# DVI.net
KiCad netlist of a schematic drawn in Altium Designer
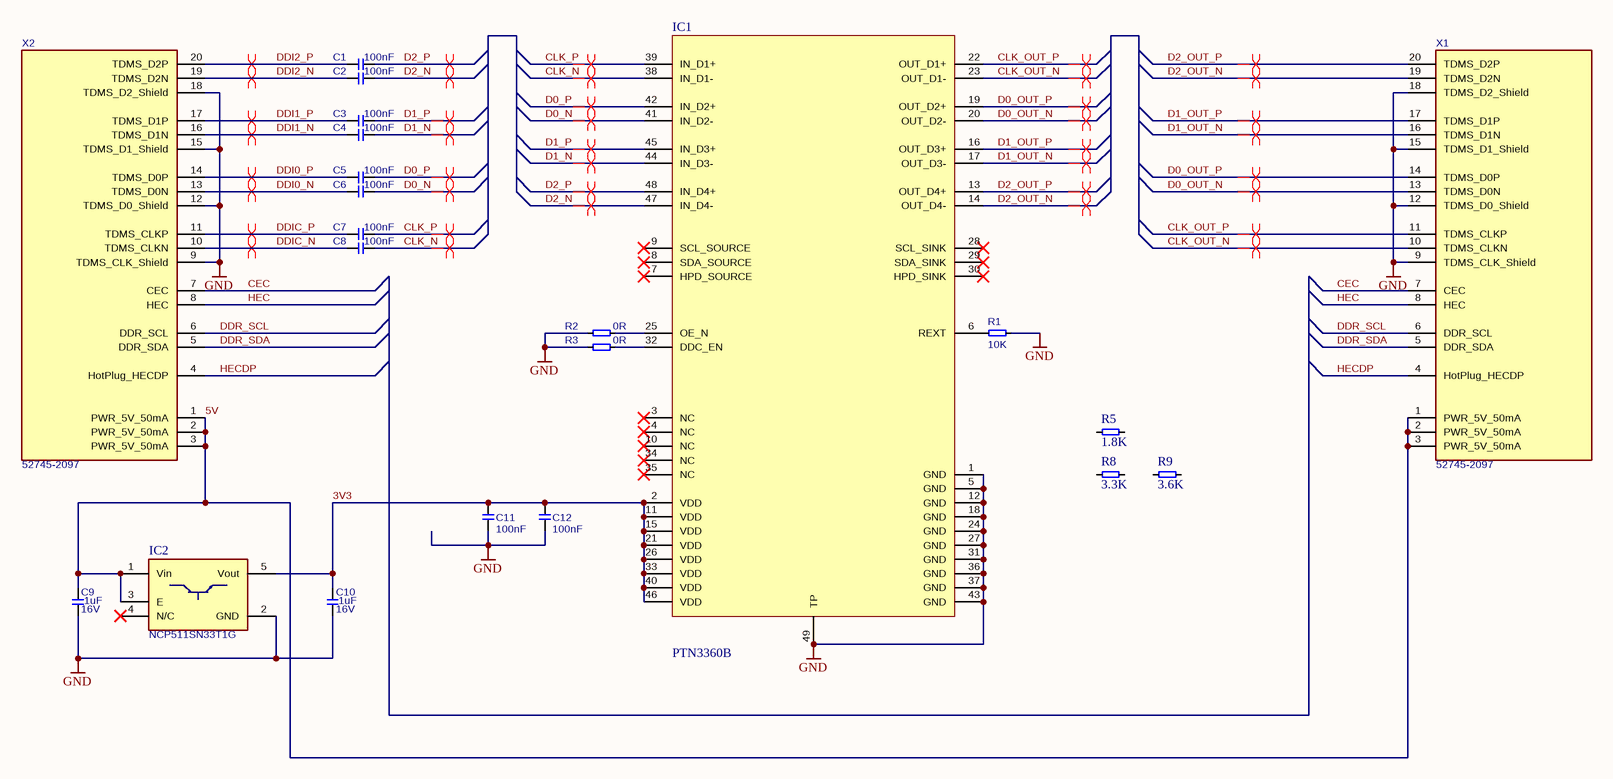
[diagram p0: DVI.SchDoc]

(export (version "E")
  (design (tool "Eeschema 10.0.6"))
  (components
    (comp (ref "C1")
      (value "100nF")
      (footprint "T_CAPC0603X33N")
      (description "Capacitor Ceramic X7R 100nF 16V 10% 0402")
      (fields (field (name "TOLERANCE") "10%"))
      (libsource (lib "Apalis Evaluation Board") (part "C-X7R-100nF-16V-10%-0402"))
    )
    (comp (ref "C2")
      (value "100nF")
      (footprint "T_CAPC0603X33N")
      (description "Capacitor Ceramic X7R 100nF 16V 10% 0402")
      (fields (field (name "TOLERANCE") "10%"))
      (libsource (lib "Apalis Evaluation Board") (part "C-X7R-100nF-16V-10%-0402"))
    )
    (comp (ref "C3")
      (value "100nF")
      (footprint "T_CAPC0603X33N")
      (description "Capacitor Ceramic X7R 100nF 16V 10% 0402")
      (fields (field (name "TOLERANCE") "10%"))
      (libsource (lib "Apalis Evaluation Board") (part "C-X7R-100nF-16V-10%-0402"))
    )
    (comp (ref "C4")
      (value "100nF")
      (footprint "T_CAPC0603X33N")
      (description "Capacitor Ceramic X7R 100nF 16V 10% 0402")
      (fields (field (name "TOLERANCE") "10%"))
      (libsource (lib "Apalis Evaluation Board") (part "C-X7R-100nF-16V-10%-0402"))
    )
    (comp (ref "C5")
      (value "100nF")
      (footprint "T_CAPC0603X33N")
      (description "Capacitor Ceramic X7R 100nF 16V 10% 0402")
      (fields (field (name "TOLERANCE") "10%"))
      (libsource (lib "Apalis Evaluation Board") (part "C-X7R-100nF-16V-10%-0402"))
    )
    (comp (ref "C6")
      (value "100nF")
      (footprint "T_CAPC0603X33N")
      (description "Capacitor Ceramic X7R 100nF 16V 10% 0402")
      (fields (field (name "TOLERANCE") "10%"))
      (libsource (lib "Apalis Evaluation Board") (part "C-X7R-100nF-16V-10%-0402"))
    )
    (comp (ref "C7")
      (value "100nF")
      (footprint "T_CAPC0603X33N")
      (description "Capacitor Ceramic X7R 100nF 16V 10% 0402")
      (fields (field (name "TOLERANCE") "10%"))
      (libsource (lib "Apalis Evaluation Board") (part "C-X7R-100nF-16V-10%-0402"))
    )
    (comp (ref "C8")
      (value "100nF")
      (footprint "T_CAPC0603X33N")
      (description "Capacitor Ceramic X7R 100nF 16V 10% 0402")
      (fields (field (name "TOLERANCE") "10%"))
      (libsource (lib "Apalis Evaluation Board") (part "C-X7R-100nF-16V-10%-0402"))
    )
    (comp (ref "C9")
      (value "1uF")
      (footprint "T_CAPC0603X33N")
      (description "Capacitor Ceramic X5R 1uF 16V 20% 0603")
      (fields (field (name "TOLERANCE") "20%") (field (name "RATING") "16V"))
      (libsource (lib "Apalis Evaluation Board") (part "C-X5R-1uF-16V-20%-0603"))
    )
    (comp (ref "C10")
      (value "1uF")
      (footprint "T_CAPC0603X33N")
      (description "Capacitor Ceramic X5R 1uF 16V 20% 0603")
      (fields (field (name "TOLERANCE") "20%") (field (name "RATING") "16V"))
      (libsource (lib "Apalis Evaluation Board") (part "C-X5R-1uF-16V-20%-0603"))
    )
    (comp (ref "C11")
      (value "100nF")
      (footprint "T_CAPC0603X33N")
      (description "Capacitor Ceramic X7R 100nF 16V 10% 0402")
      (fields (field (name "TOLERANCE") "10%"))
      (libsource (lib "Apalis Evaluation Board") (part "C-X7R-100nF-16V-10%-0402"))
    )
    (comp (ref "C12")
      (value "100nF")
      (footprint "T_CAPC0603X33N")
      (description "Capacitor Ceramic X7R 100nF 16V 10% 0402")
      (fields (field (name "TOLERANCE") "10%"))
      (libsource (lib "Apalis Evaluation Board") (part "C-X7R-100nF-16V-10%-0402"))
    )
    (comp (ref "IC1")
      (value "PTN3360B")
      (footprint "TSQFP50P900X900X160-48N_TP")
      (description "PTN3360BBS,518")
      (libsource (lib "Apalis Evaluation Board") (part "IC-NXP-PTN3360B"))
    )
    (comp (ref "IC2")
      (value "NCP511SN33T1G")
      (footprint "SOT95P279X142-5N")
      (description "NCP511SN33T1G LDO Regulator")
      (fields (field (name "MANUFACTURER PART NO.") "NCP511SN33T1G"))
      (libsource (lib "Apalis Evaluation Board") (part "IC-ON-NCP511SN33T1G"))
    )
    (comp (ref "R1")
      (value "10K")
      (footprint "T_RESC0603X30N")
      (description "Resistor 10 Kohm 63mW 1% 0603")
      (fields (field (name "TOLERANCE") "1%"))
      (libsource (lib "Apalis Evaluation Board") (part "R-10KR-63mW-1%-0603"))
    )
    (comp (ref "R2")
      (value "0R")
      (footprint "T_RESC0603X30N")
      (description "Resistor 0 ohm 63mW 1% 0603")
      (fields (field (name "TOLERANCE") "1%"))
      (libsource (lib "Apalis Evaluation Board") (part "R-0R-63mW-1%-0603"))
    )
    (comp (ref "R3")
      (value "0R")
      (footprint "T_RESC0603X30N")
      (description "Resistor 0 ohm 63mW 1% 0603")
      (fields (field (name "TOLERANCE") "1%"))
      (libsource (lib "Apalis Evaluation Board") (part "R-0R-63mW-1%-0603"))
    )
    (comp (ref "R5")
      (value "1.8K")
      (footprint "T_RESC0603X30N")
      (description "Resistor 1.8 Kohm 63mW 5% 0603")
      (fields (field (name "TOLERANCE") "5%"))
      (libsource (lib "Apalis Evaluation Board") (part "R-1.8KR-63mW-5%-0603"))
    )
    (comp (ref "R8")
      (value "3.3K")
      (footprint "T_RESC0603X30N")
      (description "Resistor 3.3 Kohm 63mW 1% 0603")
      (fields (field (name "TOLERANCE") "1%"))
      (libsource (lib "Apalis Evaluation Board") (part "R-3.3KR-63mW-1%-0603"))
    )
    (comp (ref "R9")
      (value "3.6K")
      (footprint "T_RESC0603X30N")
      (description "Resistor 3.6 Kohm 100mW 1% 0603")
      (fields (field (name "TOLERANCE") "1%"))
      (libsource (lib "Apalis Evaluation Board") (part "R-3.6KR-63mW-1%-0603"))
    )
    (comp (ref "X1")
      (value "52745-2097")
      (footprint "T_MOLEX_52745-2097_MIRROR")
      (description "0.50mm Pitch FFC/FPC DVI Connector")
      (fields (field (name "MANUFACTURER PART NO.") "52745-2097"))
      (libsource (lib "Apalis Evaluation Board") (part "CON-Molex-52745-2097-20-0.5mm"))
    )
    (comp (ref "X2")
      (value "52745-2097")
      (footprint "T_MOLEX_52745-2097")
      (description "0.50mm Pitch FFC/FPC DVI Connector")
      (fields (field (name "MANUFACTURER PART NO.") "52745-2097"))
      (libsource (lib "") (part "CON-Molex-52745-2097-20-0.5mm_1"))
    )
  )
  (nets
    (net (code "1") (name "/3V3") (class "Default")
      (node (ref "C10") (pin "2") (pinfunction "2_2") (pintype "passive"))
      (node (ref "C11") (pin "2") (pinfunction "2_2") (pintype "passive"))
      (node (ref "C12") (pin "2") (pinfunction "2_2") (pintype "passive"))
      (node (ref "IC1") (pin "11") (pinfunction "VDD_11") (pintype "passive"))
      (node (ref "IC1") (pin "15") (pinfunction "VDD_15") (pintype "passive"))
      (node (ref "IC1") (pin "2") (pinfunction "VDD_2") (pintype "passive"))
      (node (ref "IC1") (pin "21") (pinfunction "VDD_21") (pintype "passive"))
      (node (ref "IC1") (pin "26") (pinfunction "VDD_26") (pintype "passive"))
      (node (ref "IC1") (pin "33") (pinfunction "VDD_33") (pintype "passive"))
      (node (ref "IC1") (pin "40") (pinfunction "VDD_40") (pintype "passive"))
      (node (ref "IC1") (pin "46") (pinfunction "VDD_46") (pintype "passive"))
      (node (ref "IC2") (pin "5") (pinfunction "Vout_5") (pintype "passive"))
    )
    (net (code "2") (name "/5V") (class "Default")
      (node (ref "C9") (pin "2") (pinfunction "2_2") (pintype "passive"))
      (node (ref "IC2") (pin "1") (pinfunction "Vin_1") (pintype "passive"))
      (node (ref "IC2") (pin "3") (pinfunction "E_3") (pintype "passive"))
      (node (ref "X1") (pin "1") (pinfunction "PWR_5V_50mA_1") (pintype "passive"))
      (node (ref "X1") (pin "2") (pinfunction "PWR_5V_50mA_2") (pintype "passive"))
      (node (ref "X1") (pin "3") (pinfunction "PWR_5V_50mA_3") (pintype "passive"))
      (node (ref "X2") (pin "1") (pinfunction "PWR_5V_50mA_1") (pintype "passive"))
      (node (ref "X2") (pin "2") (pinfunction "PWR_5V_50mA_2") (pintype "passive"))
      (node (ref "X2") (pin "3") (pinfunction "PWR_5V_50mA_3") (pintype "passive"))
    )
    (net (code "3") (name "/CEC") (class "Default")
      (node (ref "X1") (pin "7") (pinfunction "CEC_7") (pintype "passive"))
      (node (ref "X2") (pin "7") (pinfunction "CEC_7") (pintype "passive"))
    )
    (net (code "4") (name "/CLK_N") (class "Default")
      (node (ref "C8") (pin "2") (pinfunction "2_2") (pintype "passive"))
      (node (ref "IC1") (pin "38") (pinfunction "IN_D1-_38") (pintype "passive"))
    )
    (net (code "5") (name "/CLK_OUT_N") (class "Default")
      (node (ref "IC1") (pin "23") (pinfunction "OUT_D1-_23") (pintype "passive"))
      (node (ref "X1") (pin "10") (pinfunction "TDMS_CLKN_10") (pintype "passive"))
    )
    (net (code "6") (name "/CLK_OUT_P") (class "Default")
      (node (ref "IC1") (pin "22") (pinfunction "OUT_D1+_22") (pintype "passive"))
      (node (ref "X1") (pin "11") (pinfunction "TDMS_CLKP_11") (pintype "passive"))
    )
    (net (code "7") (name "/CLK_P") (class "Default")
      (node (ref "C7") (pin "2") (pinfunction "2_2") (pintype "passive"))
      (node (ref "IC1") (pin "39") (pinfunction "IN_D1+_39") (pintype "passive"))
    )
    (net (code "8") (name "/D0_N") (class "Default")
      (node (ref "C6") (pin "2") (pinfunction "2_2") (pintype "passive"))
      (node (ref "IC1") (pin "41") (pinfunction "IN_D2-_41") (pintype "passive"))
    )
    (net (code "9") (name "/D0_OUT_N") (class "Default")
      (node (ref "IC1") (pin "20") (pinfunction "OUT_D2-_20") (pintype "passive"))
      (node (ref "X1") (pin "13") (pinfunction "TDMS_D0N_13") (pintype "passive"))
    )
    (net (code "10") (name "/D0_OUT_P") (class "Default")
      (node (ref "IC1") (pin "19") (pinfunction "OUT_D2+_19") (pintype "passive"))
      (node (ref "X1") (pin "14") (pinfunction "TDMS_D0P_14") (pintype "passive"))
    )
    (net (code "11") (name "/D0_P") (class "Default")
      (node (ref "C5") (pin "2") (pinfunction "2_2") (pintype "passive"))
      (node (ref "IC1") (pin "42") (pinfunction "IN_D2+_42") (pintype "passive"))
    )
    (net (code "12") (name "/D1_N") (class "Default")
      (node (ref "C4") (pin "2") (pinfunction "2_2") (pintype "passive"))
      (node (ref "IC1") (pin "44") (pinfunction "IN_D3-_44") (pintype "passive"))
    )
    (net (code "13") (name "/D1_OUT_N") (class "Default")
      (node (ref "IC1") (pin "17") (pinfunction "OUT_D3-_17") (pintype "passive"))
      (node (ref "X1") (pin "16") (pinfunction "TDMS_D1N_16") (pintype "passive"))
    )
    (net (code "14") (name "/D1_OUT_P") (class "Default")
      (node (ref "IC1") (pin "16") (pinfunction "OUT_D3+_16") (pintype "passive"))
      (node (ref "X1") (pin "17") (pinfunction "TDMS_D1P_17") (pintype "passive"))
    )
    (net (code "15") (name "/D1_P") (class "Default")
      (node (ref "C3") (pin "2") (pinfunction "2_2") (pintype "passive"))
      (node (ref "IC1") (pin "45") (pinfunction "IN_D3+_45") (pintype "passive"))
    )
    (net (code "16") (name "/D2_N") (class "Default")
      (node (ref "C2") (pin "2") (pinfunction "2_2") (pintype "passive"))
      (node (ref "IC1") (pin "47") (pinfunction "IN_D4-_47") (pintype "passive"))
    )
    (net (code "17") (name "/D2_OUT_N") (class "Default")
      (node (ref "IC1") (pin "14") (pinfunction "OUT_D4-_14") (pintype "passive"))
      (node (ref "X1") (pin "19") (pinfunction "TDMS_D2N_19") (pintype "passive"))
    )
    (net (code "18") (name "/D2_OUT_P") (class "Default")
      (node (ref "IC1") (pin "13") (pinfunction "OUT_D4+_13") (pintype "passive"))
      (node (ref "X1") (pin "20") (pinfunction "TDMS_D2P_20") (pintype "passive"))
    )
    (net (code "19") (name "/D2_P") (class "Default")
      (node (ref "C1") (pin "2") (pinfunction "2_2") (pintype "passive"))
      (node (ref "IC1") (pin "48") (pinfunction "IN_D4+_48") (pintype "passive"))
    )
    (net (code "20") (name "/DDI0_N") (class "Default")
      (node (ref "C6") (pin "1") (pinfunction "1_1") (pintype "passive"))
      (node (ref "X2") (pin "13") (pinfunction "TDMS_D0N_13") (pintype "passive"))
    )
    (net (code "21") (name "/DDI0_P") (class "Default")
      (node (ref "C5") (pin "1") (pinfunction "1_1") (pintype "passive"))
      (node (ref "X2") (pin "14") (pinfunction "TDMS_D0P_14") (pintype "passive"))
    )
    (net (code "22") (name "/DDI1_N") (class "Default")
      (node (ref "C4") (pin "1") (pinfunction "1_1") (pintype "passive"))
      (node (ref "X2") (pin "16") (pinfunction "TDMS_D1N_16") (pintype "passive"))
    )
    (net (code "23") (name "/DDI1_P") (class "Default")
      (node (ref "C3") (pin "1") (pinfunction "1_1") (pintype "passive"))
      (node (ref "X2") (pin "17") (pinfunction "TDMS_D1P_17") (pintype "passive"))
    )
    (net (code "24") (name "/DDI2_N") (class "Default")
      (node (ref "C2") (pin "1") (pinfunction "1_1") (pintype "passive"))
      (node (ref "X2") (pin "19") (pinfunction "TDMS_D2N_19") (pintype "passive"))
    )
    (net (code "25") (name "/DDI2_P") (class "Default")
      (node (ref "C1") (pin "1") (pinfunction "1_1") (pintype "passive"))
      (node (ref "X2") (pin "20") (pinfunction "TDMS_D2P_20") (pintype "passive"))
    )
    (net (code "26") (name "/DDIC_N") (class "Default")
      (node (ref "C8") (pin "1") (pinfunction "1_1") (pintype "passive"))
      (node (ref "X2") (pin "10") (pinfunction "TDMS_CLKN_10") (pintype "passive"))
    )
    (net (code "27") (name "/DDIC_P") (class "Default")
      (node (ref "C7") (pin "1") (pinfunction "1_1") (pintype "passive"))
      (node (ref "X2") (pin "11") (pinfunction "TDMS_CLKP_11") (pintype "passive"))
    )
    (net (code "28") (name "/DDR_SCL") (class "Default")
      (node (ref "X1") (pin "6") (pinfunction "DDR_SCL_6") (pintype "passive"))
      (node (ref "X2") (pin "6") (pinfunction "DDR_SCL_6") (pintype "passive"))
    )
    (net (code "29") (name "/DDR_SDA") (class "Default")
      (node (ref "X1") (pin "5") (pinfunction "DDR_SDA_5") (pintype "passive"))
      (node (ref "X2") (pin "5") (pinfunction "DDR_SDA_5") (pintype "passive"))
    )
    (net (code "30") (name "/HEC") (class "Default")
      (node (ref "X1") (pin "8") (pinfunction "HEC_8") (pintype "passive"))
      (node (ref "X2") (pin "8") (pinfunction "HEC_8") (pintype "passive"))
    )
    (net (code "31") (name "/HECDP") (class "Default")
      (node (ref "X1") (pin "4") (pinfunction "HotPlug_HECDP_4") (pintype "passive"))
      (node (ref "X2") (pin "4") (pinfunction "HotPlug_HECDP_4") (pintype "passive"))
    )
    (net (code "32") (name "GND") (class "Default")
      (node (ref "C10") (pin "1") (pinfunction "1_1") (pintype "passive"))
      (node (ref "C11") (pin "1") (pinfunction "1_1") (pintype "passive"))
      (node (ref "C12") (pin "1") (pinfunction "1_1") (pintype "passive"))
      (node (ref "C9") (pin "1") (pinfunction "1_1") (pintype "passive"))
      (node (ref "IC1") (pin "1") (pinfunction "GND_1") (pintype "passive"))
      (node (ref "IC1") (pin "12") (pinfunction "GND_12") (pintype "passive"))
      (node (ref "IC1") (pin "18") (pinfunction "GND_18") (pintype "passive"))
      (node (ref "IC1") (pin "24") (pinfunction "GND_24") (pintype "passive"))
      (node (ref "IC1") (pin "27") (pinfunction "GND_27") (pintype "passive"))
      (node (ref "IC1") (pin "31") (pinfunction "GND_31") (pintype "passive"))
      (node (ref "IC1") (pin "36") (pinfunction "GND_36") (pintype "passive"))
      (node (ref "IC1") (pin "37") (pinfunction "GND_37") (pintype "passive"))
      (node (ref "IC1") (pin "43") (pinfunction "GND_43") (pintype "passive"))
      (node (ref "IC1") (pin "49") (pinfunction "TP_49") (pintype "passive"))
      (node (ref "IC1") (pin "5") (pinfunction "GND_5") (pintype "passive"))
      (node (ref "IC2") (pin "2") (pinfunction "GND_2") (pintype "passive"))
      (node (ref "R1") (pin "2") (pinfunction "2_2") (pintype "passive"))
      (node (ref "R2") (pin "1") (pinfunction "1_1") (pintype "passive"))
      (node (ref "R3") (pin "1") (pinfunction "1_1") (pintype "passive"))
      (node (ref "X1") (pin "12") (pinfunction "TDMS_D0_Shield_12") (pintype "passive"))
      (node (ref "X1") (pin "15") (pinfunction "TDMS_D1_Shield_15") (pintype "passive"))
      (node (ref "X1") (pin "18") (pinfunction "TDMS_D2_Shield_18") (pintype "passive"))
      (node (ref "X1") (pin "9") (pinfunction "TDMS_CLK_Shield_9") (pintype "passive"))
      (node (ref "X2") (pin "12") (pinfunction "TDMS_D0_Shield_12") (pintype "passive"))
      (node (ref "X2") (pin "15") (pinfunction "TDMS_D1_Shield_15") (pintype "passive"))
      (node (ref "X2") (pin "18") (pinfunction "TDMS_D2_Shield_18") (pintype "passive"))
      (node (ref "X2") (pin "9") (pinfunction "TDMS_CLK_Shield_9") (pintype "passive"))
    )
    (net (code "33") (name "Net-(IC1-DDC_EN)") (class "Default")
      (node (ref "IC1") (pin "32") (pinfunction "DDC_EN_32") (pintype "passive"))
      (node (ref "R3") (pin "2") (pinfunction "2_2") (pintype "passive"))
    )
    (net (code "34") (name "Net-(IC1-OE_N)") (class "Default")
      (node (ref "IC1") (pin "25") (pinfunction "OE_N_25") (pintype "passive"))
      (node (ref "R2") (pin "2") (pinfunction "2_2") (pintype "passive"))
    )
    (net (code "35") (name "Net-(IC1-REXT)") (class "Default")
      (node (ref "IC1") (pin "6") (pinfunction "REXT_6") (pintype "passive"))
      (node (ref "R1") (pin "1") (pinfunction "1_1") (pintype "passive"))
    )
    (net (code "36") (name "unconnected-(IC1-HPD_SINK-Pad30)") (class "Default")
      (node (ref "IC1") (pin "30") (pinfunction "HPD_SINK_30") (pintype "passive+no_connect"))
    )
    (net (code "37") (name "unconnected-(IC1-HPD_SOURCE-Pad7)") (class "Default")
      (node (ref "IC1") (pin "7") (pinfunction "HPD_SOURCE_7") (pintype "passive+no_connect"))
    )
    (net (code "38") (name "unconnected-(IC1-NC-Pad3)") (class "Default")
      (node (ref "IC1") (pin "3") (pinfunction "NC_3") (pintype "passive+no_connect"))
    )
    (net (code "39") (name "unconnected-(IC1-NC-Pad4)") (class "Default")
      (node (ref "IC1") (pin "4") (pinfunction "NC_4") (pintype "passive+no_connect"))
    )
    (net (code "40") (name "unconnected-(IC1-NC-Pad10)") (class "Default")
      (node (ref "IC1") (pin "10") (pinfunction "NC_10") (pintype "passive+no_connect"))
    )
    (net (code "41") (name "unconnected-(IC1-NC-Pad34)") (class "Default")
      (node (ref "IC1") (pin "34") (pinfunction "NC_34") (pintype "passive+no_connect"))
    )
    (net (code "42") (name "unconnected-(IC1-NC-Pad35)") (class "Default")
      (node (ref "IC1") (pin "35") (pinfunction "NC_35") (pintype "passive+no_connect"))
    )
    (net (code "43") (name "unconnected-(IC1-SCL_SINK-Pad28)") (class "Default")
      (node (ref "IC1") (pin "28") (pinfunction "SCL_SINK_28") (pintype "passive+no_connect"))
    )
    (net (code "44") (name "unconnected-(IC1-SCL_SOURCE-Pad9)") (class "Default")
      (node (ref "IC1") (pin "9") (pinfunction "SCL_SOURCE_9") (pintype "passive+no_connect"))
    )
    (net (code "45") (name "unconnected-(IC1-SDA_SINK-Pad29)") (class "Default")
      (node (ref "IC1") (pin "29") (pinfunction "SDA_SINK_29") (pintype "passive+no_connect"))
    )
    (net (code "46") (name "unconnected-(IC1-SDA_SOURCE-Pad8)") (class "Default")
      (node (ref "IC1") (pin "8") (pinfunction "SDA_SOURCE_8") (pintype "passive+no_connect"))
    )
    (net (code "47") (name "unconnected-(IC2-N{slash}C-Pad4)") (class "Default")
      (node (ref "IC2") (pin "4") (pinfunction "N/C_4") (pintype "passive+no_connect"))
    )
    (net (code "48") (name "unconnected-(R5-Pad1)") (class "Default")
      (node (ref "R5") (pin "1") (pinfunction "1_1") (pintype "passive"))
    )
    (net (code "49") (name "unconnected-(R5-Pad2)") (class "Default")
      (node (ref "R5") (pin "2") (pinfunction "2_2") (pintype "passive"))
    )
    (net (code "50") (name "unconnected-(R8-Pad1)") (class "Default")
      (node (ref "R8") (pin "1") (pinfunction "1_1") (pintype "passive"))
    )
    (net (code "51") (name "unconnected-(R8-Pad2)") (class "Default")
      (node (ref "R8") (pin "2") (pinfunction "2_2") (pintype "passive"))
    )
    (net (code "52") (name "unconnected-(R9-Pad1)") (class "Default")
      (node (ref "R9") (pin "1") (pinfunction "1_1") (pintype "passive"))
    )
    (net (code "53") (name "unconnected-(R9-Pad2)") (class "Default")
      (node (ref "R9") (pin "2") (pinfunction "2_2") (pintype "passive"))
    )
  )
)
